# DC-DC_-5V.net
KiCad netlist of a schematic drawn in Altium Designer
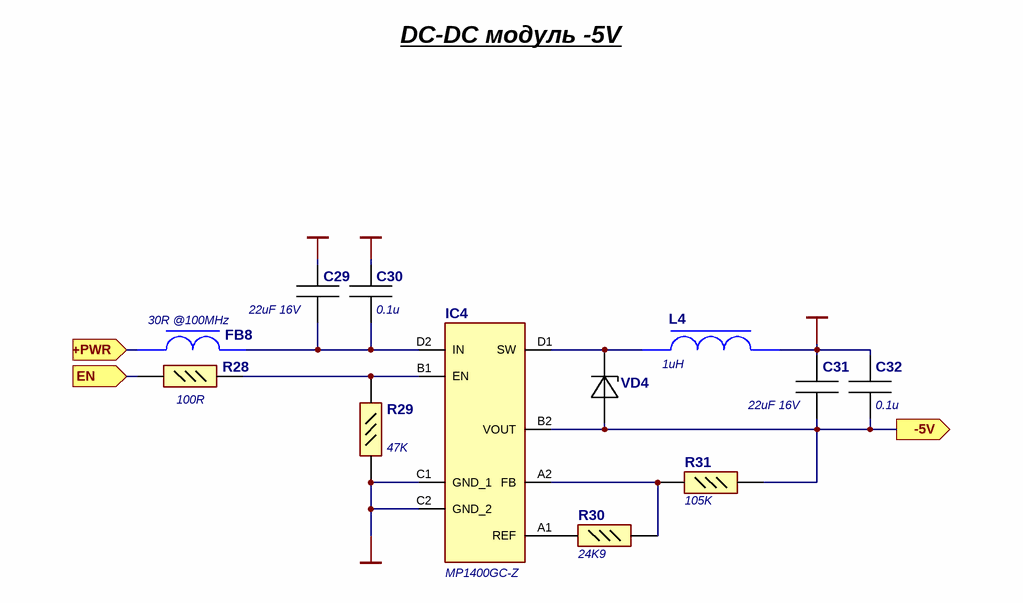
[diagram p0: DC-DC модуль -5V.SchDoc]

(export (version "E")
  (design (tool "Eeschema 10.0.6"))
  (components
    (comp (ref "C29")
      (value "22uF 16V")
      (footprint ":CAP0805 C2012X125")
      (description "CAP CER 22uF 16V X5R")
      (fields
        (field (name "MANUFACTURER_PART_NUMBER") "GRM21BR61C226ME44L")
        (field (name "MOUSER PART NUMBER") "81-GRM21BR61C226ME4L")
      )
      (libsource (lib "Capacitors 0805") (part "GRM21BR61C226ME44L"))
    )
    (comp (ref "C30")
      (value "0.1u")
      (footprint ":CAP0402 100x50x50")
      (description "±10% 25V Ceramic Capacitor X7R 0402 (1005 Metric)")
      (fields
        (field (name "MANUFACTURER_PART_NUMBER") "GRM155R71E104KE14J")
        (field (name "MOUSER PART NUMBER") "81-GRM155R71E104KE4J")
      )
      (libsource (lib "Capacitors 0402") (part "GRM155R71E104KE14J"))
    )
    (comp (ref "C31")
      (value "22uF 16V")
      (footprint ":CAP0805 C2012X125")
      (description "CAP CER 22uF 16V X5R")
      (fields
        (field (name "MANUFACTURER_PART_NUMBER") "GRM21BR61C226ME44L")
        (field (name "MOUSER PART NUMBER") "81-GRM21BR61C226ME4L")
      )
      (libsource (lib "Capacitors 0805") (part "GRM21BR61C226ME44L"))
    )
    (comp (ref "C32")
      (value "0.1u")
      (footprint ":CAP0402 100x50x50")
      (description "±10% 25V Ceramic Capacitor X7R 0402 (1005 Metric)")
      (fields
        (field (name "MANUFACTURER_PART_NUMBER") "GRM155R71E104KE14J")
        (field (name "MOUSER PART NUMBER") "81-GRM155R71E104KE4J")
      )
      (libsource (lib "Capacitors 0402") (part "GRM155R71E104KE14J"))
    )
    (comp (ref "FB8")
      (value "30R @100MHz")
      (footprint ":FER BLM18SP300SN1D")
      (description "30 Ohms @ 100MHz 1 Power Line Ferrite Bead 0603 (1608 Metric) 6A 8mOhm")
      (fields
        (field (name "MANUFACTURER_PART_NUMBER") "BLM18SP300SN1D")
        (field (name "MOUSER PART NUMBER") "81-BLM18SP300SN1D")
      )
      (libsource (lib "Ferrite Bead") (part "BLM18SP300SN1D"))
    )
    (comp (ref "IC4")
      (value "MP1400GC-Z")
      (footprint ":BGA8 CSP P2X4_80X160X63")
      (description "DC/DC Converter \r\nInput 2.7V...7V\r\nOutput -0.9V...-6V 600mA")
      (libsource (lib "DC-DC convertors") (part "MP1400GC-Z"))
    )
    (comp (ref "L4")
      (value "1uH")
      (footprint ":IND1210 C3225")
      (fields (field (name "MANUFACTURER_PART_NUMBER") "74479299210"))
      (libsource (lib "Inductance") (part "74479299210"))
    )
    (comp (ref "R28")
      (value "RC0402FR-07")
      (footprint ":RES0402")
      (fields (field (name "MANUFACTURER_PART_NUMBER (PART 2: VALUE)") "100R"))
      (libsource (lib "Resistors 0402") (part "RC0402FR-07"))
    )
    (comp (ref "R29")
      (value "RC0402FR-07")
      (footprint ":RES0402")
      (fields (field (name "MANUFACTURER_PART_NUMBER (PART 2: VALUE)") "47K"))
      (libsource (lib "") (part "RC0402FR-07_1"))
    )
    (comp (ref "R30")
      (value "RC0402FR-07")
      (footprint ":RES0402")
      (fields (field (name "MANUFACTURER_PART_NUMBER (PART 2: VALUE)") "24K9"))
      (libsource (lib "Resistors 0402") (part "RC0402FR-07"))
    )
    (comp (ref "R31")
      (value "RC0402FR-07")
      (footprint ":RES0402")
      (fields (field (name "MANUFACTURER_PART_NUMBER (PART 2: VALUE)") "105K"))
      (libsource (lib "Resistors 0402") (part "RC0402FR-07"))
    )
    (comp (ref "VD4")
      (value "40V 1.5A")
      (footprint ":DIODE CST2C")
      (description "Diode Schottky 40V 1.5A\r\n@If 550mV @ 1.5A\r\n@Vr 200µA @ 40V")
      (fields (field (name "MANUFACTURER_PART_NUMBER") "CCS15S40,L3F"))
      (libsource (lib "Diodes 0603") (part "CCS15S40,L3F"))
    )
  )
  (nets
    (net (code "1") (name "/+PWR") (class "Default")
      (node (ref "FB8") (pin "1") (pinfunction "1_1") (pintype "passive"))
    )
    (net (code "2") (name "/-5V") (class "Default")
      (node (ref "C31") (pin "1") (pinfunction "1_1") (pintype "passive"))
      (node (ref "C32") (pin "2") (pinfunction "2_2") (pintype "passive"))
      (node (ref "IC4") (pin "B2") (pinfunction "VOUT_B2") (pintype "passive"))
      (node (ref "R31") (pin "2") (pinfunction "2_2") (pintype "passive"))
      (node (ref "VD4") (pin "2") (pinfunction "A_2") (pintype "passive"))
    )
    (net (code "3") (name "/EN") (class "Default")
      (node (ref "R28") (pin "1") (pinfunction "1_1") (pintype "passive"))
    )
    (net (code "4") (name "GND") (class "Default")
      (node (ref "C29") (pin "2") (pinfunction "2_2") (pintype "passive"))
      (node (ref "C30") (pin "1") (pinfunction "1_1") (pintype "passive"))
      (node (ref "C31") (pin "2") (pinfunction "2_2") (pintype "passive"))
      (node (ref "C32") (pin "1") (pinfunction "1_1") (pintype "passive"))
      (node (ref "IC4") (pin "C1") (pinfunction "GND_1_C1") (pintype "passive"))
      (node (ref "IC4") (pin "C2") (pinfunction "GND_2_C2") (pintype "passive"))
      (node (ref "L4") (pin "2") (pinfunction "2_2") (pintype "passive"))
      (node (ref "R29") (pin "1") (pinfunction "1_1") (pintype "passive"))
    )
    (net (code "5") (name "Net-(IC4-EN)") (class "Default")
      (node (ref "IC4") (pin "B1") (pinfunction "EN_B1") (pintype "passive"))
      (node (ref "R28") (pin "2") (pinfunction "2_2") (pintype "passive"))
      (node (ref "R29") (pin "2") (pinfunction "2_2") (pintype "passive"))
    )
    (net (code "6") (name "Net-(IC4-FB)") (class "Default")
      (node (ref "IC4") (pin "A2") (pinfunction "FB_A2") (pintype "passive"))
      (node (ref "R30") (pin "2") (pinfunction "2_2") (pintype "passive"))
      (node (ref "R31") (pin "1") (pinfunction "1_1") (pintype "passive"))
    )
    (net (code "7") (name "Net-(IC4-IN)") (class "Default")
      (node (ref "C29") (pin "1") (pinfunction "1_1") (pintype "passive"))
      (node (ref "C30") (pin "2") (pinfunction "2_2") (pintype "passive"))
      (node (ref "FB8") (pin "2") (pinfunction "2_2") (pintype "passive"))
      (node (ref "IC4") (pin "D2") (pinfunction "IN_D2") (pintype "passive"))
    )
    (net (code "8") (name "Net-(IC4-REF)") (class "Default")
      (node (ref "IC4") (pin "A1") (pinfunction "REF_A1") (pintype "passive"))
      (node (ref "R30") (pin "1") (pinfunction "1_1") (pintype "passive"))
    )
    (net (code "9") (name "Net-(IC4-SW)") (class "Default")
      (node (ref "IC4") (pin "D1") (pinfunction "SW_D1") (pintype "passive"))
      (node (ref "L4") (pin "1") (pinfunction "1_1") (pintype "passive"))
      (node (ref "VD4") (pin "1") (pinfunction "K_1") (pintype "passive"))
    )
  )
)
